# pcg_quad.net
KiCad netlist of a schematic drawn in EAGLE
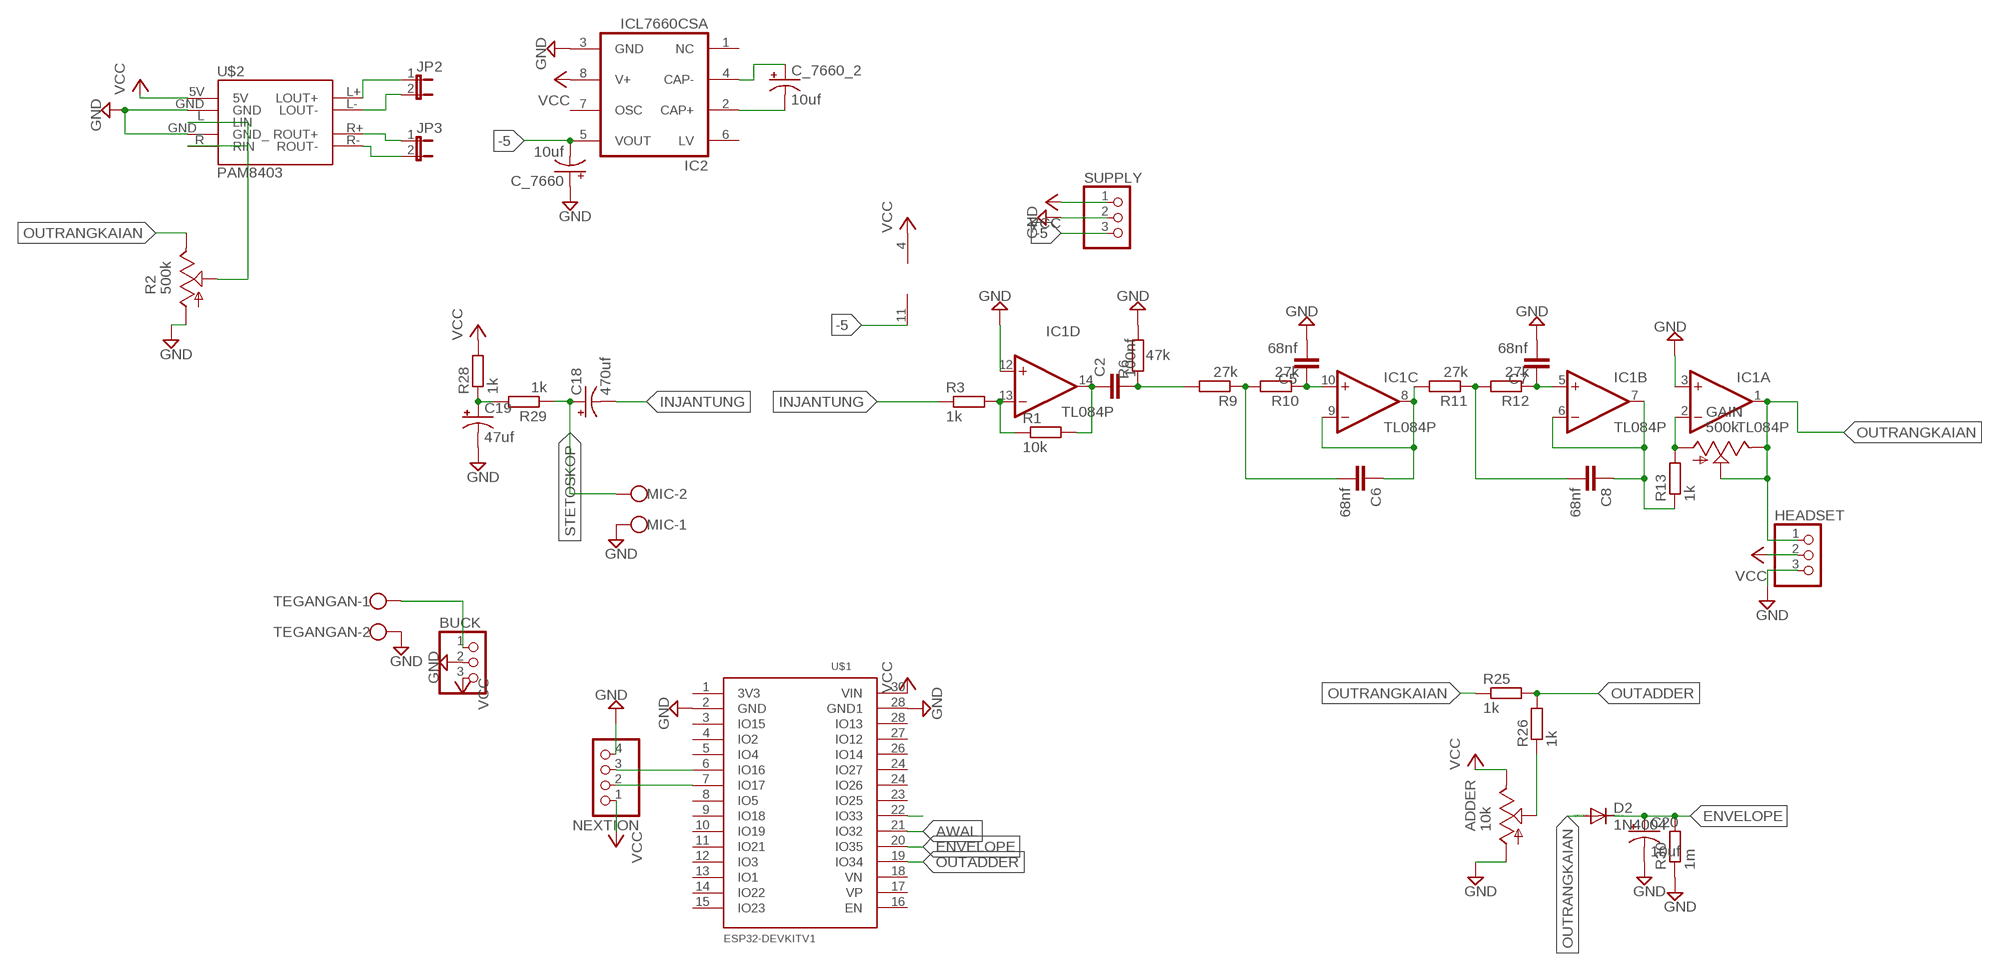
[diagram p0: schematic, sheet 1]

(export (version "E")
  (design (tool "Eeschema 10.0.6"))
  (components
    (comp (ref "ADDER")
      (value "10k")
      (footprint "eagle-import:B64Y")
      (libsource (lib "eagle-import") (part "TRIM_US-B64Y"))
    )
    (comp (ref "BUCK")
      (value "PINHD-1X3")
      (footprint "eagle-import:1X03")
      (libsource (lib "eagle-import") (part "PINHD-1X3"))
    )
    (comp (ref "C2")
      (value "100nf")
      (footprint "eagle-import:C050-025X075")
      (libsource (lib "eagle-import") (part "C-EU050-025X075"))
    )
    (comp (ref "C5")
      (value "68nf")
      (footprint "eagle-import:C050-025X075")
      (libsource (lib "eagle-import") (part "C-EU050-025X075"))
    )
    (comp (ref "C6")
      (value "68nf")
      (footprint "eagle-import:C050-025X075")
      (libsource (lib "eagle-import") (part "C-EU050-025X075"))
    )
    (comp (ref "C7")
      (value "68nf")
      (footprint "eagle-import:C050-025X075")
      (libsource (lib "eagle-import") (part "C-EU050-025X075"))
    )
    (comp (ref "C8")
      (value "68nf")
      (footprint "eagle-import:C050-025X075")
      (libsource (lib "eagle-import") (part "C-EU050-025X075"))
    )
    (comp (ref "C18")
      (value "470uf")
      (footprint "eagle-import:E2,5-7")
      (libsource (lib "eagle-import") (part "CPOL-USE2.5-7"))
    )
    (comp (ref "C19")
      (value "47uf")
      (footprint "eagle-import:E2-5")
      (libsource (lib "eagle-import") (part "CPOL-USE2-5"))
    )
    (comp (ref "C20")
      (value "10uf")
      (footprint "eagle-import:E2-5")
      (libsource (lib "eagle-import") (part "CPOL-USE2-5"))
    )
    (comp (ref "C_7660")
      (value "10uf")
      (footprint "eagle-import:E2-5")
      (libsource (lib "eagle-import") (part "CPOL-USE2-5"))
    )
    (comp (ref "C_7660_2")
      (value "10uf")
      (footprint "eagle-import:E2-5")
      (libsource (lib "eagle-import") (part "CPOL-USE2-5"))
    )
    (comp (ref "D2")
      (value "1N4004")
      (footprint "eagle-import:DO41-10")
      (libsource (lib "eagle-import") (part "1N4004"))
    )
    (comp (ref "GAIN")
      (value "500k")
      (footprint "eagle-import:B64Y")
      (libsource (lib "eagle-import") (part "TRIM_US-B64Y"))
    )
    (comp (ref "HEADSET")
      (value "PINHD-1X3")
      (footprint "eagle-import:1X03")
      (libsource (lib "eagle-import") (part "PINHD-1X3"))
    )
    (comp (ref "IC1")
      (value "TL084P")
      (footprint "eagle-import:DIL14")
      (libsource (lib "eagle-import") (part "TL084P"))
    )
    (comp (ref "IC2")
      (value "ICL7660CSA")
      (footprint "eagle-import:SO08")
      (fields (field (name "MF") "MAXIM"))
      (libsource (lib "eagle-import") (part "ICL7660CSA"))
    )
    (comp (ref "JP2")
      (value "JP1E")
      (footprint "eagle-import:JP1")
      (libsource (lib "eagle-import") (part "JP1E"))
    )
    (comp (ref "JP3")
      (value "JP1E")
      (footprint "eagle-import:JP1")
      (libsource (lib "eagle-import") (part "JP1E"))
    )
    (comp (ref "MIC")
      (value "W237-102")
      (footprint "eagle-import:W237-102")
      (fields (field (name "MPN") "237-102"))
      (libsource (lib "eagle-import") (part "W237-102"))
    )
    (comp (ref "NEXTION")
      (value "PINHD-1X4")
      (footprint "eagle-import:1X04")
      (libsource (lib "eagle-import") (part "PINHD-1X4"))
    )
    (comp (ref "R1")
      (value "10k")
      (footprint "eagle-import:0309_10")
      (libsource (lib "eagle-import") (part "R-EU_0309/10"))
    )
    (comp (ref "R2")
      (value "500k")
      (footprint "eagle-import:B64Y")
      (libsource (lib "eagle-import") (part "TRIM_US-B64Y"))
    )
    (comp (ref "R3")
      (value "1k")
      (footprint "eagle-import:0309_10")
      (libsource (lib "eagle-import") (part "R-EU_0309/10"))
    )
    (comp (ref "R6")
      (value "47k")
      (footprint "eagle-import:0309_10")
      (libsource (lib "eagle-import") (part "R-EU_0309/10"))
    )
    (comp (ref "R9")
      (value "27k")
      (footprint "eagle-import:0309_10")
      (libsource (lib "eagle-import") (part "R-EU_0309/10"))
    )
    (comp (ref "R10")
      (value "27k")
      (footprint "eagle-import:0309_10")
      (libsource (lib "eagle-import") (part "R-EU_0309/10"))
    )
    (comp (ref "R11")
      (value "27k")
      (footprint "eagle-import:0309_10")
      (libsource (lib "eagle-import") (part "R-EU_0309/10"))
    )
    (comp (ref "R12")
      (value "27k")
      (footprint "eagle-import:0309_10")
      (libsource (lib "eagle-import") (part "R-EU_0309/10"))
    )
    (comp (ref "R13")
      (value "1k")
      (footprint "eagle-import:0309_10")
      (libsource (lib "eagle-import") (part "R-EU_0309/10"))
    )
    (comp (ref "R25")
      (value "1k")
      (footprint "eagle-import:0309_10")
      (libsource (lib "eagle-import") (part "R-EU_0309/10"))
    )
    (comp (ref "R26")
      (value "1k")
      (footprint "eagle-import:0309_10")
      (libsource (lib "eagle-import") (part "R-EU_0309/10"))
    )
    (comp (ref "R28")
      (value "1k")
      (footprint "eagle-import:0309_10")
      (libsource (lib "eagle-import") (part "R-EU_0309/10"))
    )
    (comp (ref "R29")
      (value "1k")
      (footprint "eagle-import:0309_10")
      (libsource (lib "eagle-import") (part "R-EU_0309/10"))
    )
    (comp (ref "R30")
      (value "1m")
      (footprint "eagle-import:0309_10")
      (libsource (lib "eagle-import") (part "R-EU_0309/10"))
    )
    (comp (ref "SUPPLY")
      (value "PINHD-1X3")
      (footprint "eagle-import:1X03")
      (libsource (lib "eagle-import") (part "PINHD-1X3"))
    )
    (comp (ref "TEGANGAN")
      (value "W237-102")
      (footprint "eagle-import:W237-102")
      (fields (field (name "MPN") "237-102"))
      (libsource (lib "eagle-import") (part "W237-102"))
    )
    (comp (ref "U$1")
      (value "ESP32DEVKITV1")
      (footprint "eagle-import:ESP32-DEVKITV1")
      (libsource (lib "eagle-import") (part "ESP32DEVKITV1"))
    )
    (comp (ref "U$2")
      (value "PAM8403")
      (footprint "eagle-import:PAM8403")
      (libsource (lib "eagle-import") (part "PAM8403"))
    )
  )
  (nets
    (net (code "1") (name "-5") (class "Default")
      (node (ref "C_7660") (pin "-") (pinfunction "-_-") (pintype "passive"))
      (node (ref "IC1") (pin "11") (pinfunction "V-_11") (pintype "power_in"))
      (node (ref "IC2") (pin "5") (pinfunction "VOUT_5") (pintype "output"))
      (node (ref "SUPPLY") (pin "3") (pinfunction "3_3") (pintype "passive"))
    )
    (net (code "2") (name "AWAL") (class "Default")
      (node (ref "U$1") (pin "21") (pinfunction "IO32_21") (pintype "bidirectional"))
    )
    (net (code "3") (name "ENVELOPE") (class "Default")
      (node (ref "C20") (pin "+") (pinfunction "+_+") (pintype "passive"))
      (node (ref "D2") (pin "C") (pinfunction "C_C") (pintype "passive"))
      (node (ref "R30") (pin "2") (pinfunction "2_2") (pintype "passive"))
      (node (ref "U$1") (pin "20") (pinfunction "IO35_20") (pintype "bidirectional"))
    )
    (net (code "4") (name "GND") (class "Default")
      (node (ref "ADDER") (pin "A") (pinfunction "A_A") (pintype "passive"))
      (node (ref "BUCK") (pin "2") (pinfunction "2_2") (pintype "passive"))
      (node (ref "C19") (pin "-") (pinfunction "-_-") (pintype "passive"))
      (node (ref "C20") (pin "-") (pinfunction "-_-") (pintype "passive"))
      (node (ref "C5") (pin "2") (pinfunction "2_2") (pintype "passive"))
      (node (ref "C7") (pin "2") (pinfunction "2_2") (pintype "passive"))
      (node (ref "C_7660") (pin "+") (pinfunction "+_+") (pintype "passive"))
      (node (ref "HEADSET") (pin "3") (pinfunction "3_3") (pintype "passive"))
      (node (ref "IC1") (pin "12") (pinfunction "+IN_12") (pintype "input"))
      (node (ref "IC1") (pin "3") (pinfunction "+IN_3") (pintype "input"))
      (node (ref "IC2") (pin "3") (pinfunction "GND_3") (pintype "power_in"))
      (node (ref "MIC") (pin "1") (pinfunction "KL_1") (pintype "passive"))
      (node (ref "NEXTION") (pin "4") (pinfunction "4_4") (pintype "passive"))
      (node (ref "R2") (pin "A") (pinfunction "A_A") (pintype "passive"))
      (node (ref "R30") (pin "1") (pinfunction "1_1") (pintype "passive"))
      (node (ref "R6") (pin "2") (pinfunction "2_2") (pintype "passive"))
      (node (ref "SUPPLY") (pin "2") (pinfunction "2_2") (pintype "passive"))
      (node (ref "TEGANGAN") (pin "2") (pinfunction "KL_2") (pintype "passive"))
      (node (ref "U$1") (pin "2") (pinfunction "GND_2") (pintype "bidirectional"))
      (node (ref "U$1") (pin "28") (pinfunction "GND1_28") (pintype "bidirectional"))
      (node (ref "U$2") (pin "GND") (pinfunction "GND_GND") (pintype "bidirectional"))
      (node (ref "U$2") (pin "GND_") (pinfunction "GND__GND_") (pintype "bidirectional"))
    )
    (net (code "5") (name "INJANTUNG") (class "Default")
      (node (ref "C18") (pin "-") (pinfunction "-_-") (pintype "passive"))
      (node (ref "R3") (pin "1") (pinfunction "1_1") (pintype "passive"))
    )
    (net (code "6") (name "Net-(ADDER-PadS)") (class "Default")
      (node (ref "ADDER") (pin "S") (pinfunction "S_S") (pintype "passive"))
      (node (ref "R26") (pin "1") (pinfunction "1_1") (pintype "passive"))
    )
    (net (code "7") (name "Net-(C2-Pad2)") (class "Default")
      (node (ref "C2") (pin "2") (pinfunction "2_2") (pintype "passive"))
      (node (ref "R6") (pin "1") (pinfunction "1_1") (pintype "passive"))
      (node (ref "R9") (pin "2") (pinfunction "2_2") (pintype "passive"))
    )
    (net (code "8") (name "Net-(C6-Pad2)") (class "Default")
      (node (ref "C6") (pin "2") (pinfunction "2_2") (pintype "passive"))
      (node (ref "R10") (pin "2") (pinfunction "2_2") (pintype "passive"))
      (node (ref "R9") (pin "1") (pinfunction "1_1") (pintype "passive"))
    )
    (net (code "9") (name "Net-(C8-Pad2)") (class "Default")
      (node (ref "C8") (pin "2") (pinfunction "2_2") (pintype "passive"))
      (node (ref "R11") (pin "1") (pinfunction "1_1") (pintype "passive"))
      (node (ref "R12") (pin "2") (pinfunction "2_2") (pintype "passive"))
    )
    (net (code "10") (name "Net-(C19-Pad+)") (class "Default")
      (node (ref "C19") (pin "+") (pinfunction "+_+") (pintype "passive"))
      (node (ref "R28") (pin "1") (pinfunction "1_1") (pintype "passive"))
      (node (ref "R29") (pin "2") (pinfunction "2_2") (pintype "passive"))
    )
    (net (code "11") (name "Net-(IC1A--IN)") (class "Default")
      (node (ref "GAIN") (pin "A") (pinfunction "A_A") (pintype "passive"))
      (node (ref "IC1") (pin "2") (pinfunction "-IN_2") (pintype "input"))
      (node (ref "R13") (pin "2") (pinfunction "2_2") (pintype "passive"))
    )
    (net (code "12") (name "Net-(IC1B-+IN)") (class "Default")
      (node (ref "C7") (pin "1") (pinfunction "1_1") (pintype "passive"))
      (node (ref "IC1") (pin "5") (pinfunction "+IN_5") (pintype "input"))
      (node (ref "R12") (pin "1") (pinfunction "1_1") (pintype "passive"))
    )
    (net (code "13") (name "Net-(IC1B--IN)") (class "Default")
      (node (ref "C8") (pin "1") (pinfunction "1_1") (pintype "passive"))
      (node (ref "IC1") (pin "6") (pinfunction "-IN_6") (pintype "input"))
      (node (ref "IC1") (pin "7") (pinfunction "OUT_7") (pintype "output"))
      (node (ref "R13") (pin "1") (pinfunction "1_1") (pintype "passive"))
    )
    (net (code "14") (name "Net-(IC1C-+IN)") (class "Default")
      (node (ref "C5") (pin "1") (pinfunction "1_1") (pintype "passive"))
      (node (ref "IC1") (pin "10") (pinfunction "+IN_10") (pintype "input"))
      (node (ref "R10") (pin "1") (pinfunction "1_1") (pintype "passive"))
    )
    (net (code "15") (name "Net-(IC1C--IN)") (class "Default")
      (node (ref "C6") (pin "1") (pinfunction "1_1") (pintype "passive"))
      (node (ref "IC1") (pin "8") (pinfunction "OUT_8") (pintype "output"))
      (node (ref "IC1") (pin "9") (pinfunction "-IN_9") (pintype "input"))
      (node (ref "R11") (pin "2") (pinfunction "2_2") (pintype "passive"))
    )
    (net (code "16") (name "Net-(IC1D--IN)") (class "Default")
      (node (ref "IC1") (pin "13") (pinfunction "-IN_13") (pintype "input"))
      (node (ref "R1") (pin "1") (pinfunction "1_1") (pintype "passive"))
      (node (ref "R3") (pin "2") (pinfunction "2_2") (pintype "passive"))
    )
    (net (code "17") (name "Net-(IC1D-OUT)") (class "Default")
      (node (ref "C2") (pin "1") (pinfunction "1_1") (pintype "passive"))
      (node (ref "IC1") (pin "14") (pinfunction "OUT_14") (pintype "output"))
      (node (ref "R1") (pin "2") (pinfunction "2_2") (pintype "passive"))
    )
    (net (code "18") (name "Net-(IC2-CAP+)") (class "Default")
      (node (ref "C_7660_2") (pin "-") (pinfunction "-_-") (pintype "passive"))
      (node (ref "IC2") (pin "2") (pinfunction "CAP+_2") (pintype "passive"))
    )
    (net (code "19") (name "Net-(IC2-CAP-)") (class "Default")
      (node (ref "C_7660_2") (pin "+") (pinfunction "+_+") (pintype "passive"))
      (node (ref "IC2") (pin "4") (pinfunction "CAP-_4") (pintype "passive"))
    )
    (net (code "20") (name "Net-(TEGANGANA-KL)") (class "Default")
      (node (ref "BUCK") (pin "1") (pinfunction "1_1") (pintype "passive"))
      (node (ref "TEGANGAN") (pin "1") (pinfunction "KL_1") (pintype "passive"))
    )
    (net (code "21") (name "Net-(U$1-IO16)") (class "Default")
      (node (ref "NEXTION") (pin "3") (pinfunction "3_3") (pintype "passive"))
      (node (ref "U$1") (pin "6") (pinfunction "IO16_6") (pintype "bidirectional"))
    )
    (net (code "22") (name "Net-(U$1-IO17)") (class "Default")
      (node (ref "NEXTION") (pin "2") (pinfunction "2_2") (pintype "passive"))
      (node (ref "U$1") (pin "7") (pinfunction "IO17_7") (pintype "bidirectional"))
    )
    (net (code "23") (name "Net-(U$2-LIN)") (class "Default")
      (node (ref "R2") (pin "S") (pinfunction "S_S") (pintype "passive"))
      (node (ref "U$2") (pin "L") (pinfunction "LIN_L") (pintype "bidirectional"))
      (node (ref "U$2") (pin "R") (pinfunction "RIN_R") (pintype "bidirectional"))
    )
    (net (code "24") (name "Net-(U$2-LOUT+)") (class "Default")
      (node (ref "JP2") (pin "1") (pinfunction "1_1") (pintype "passive"))
      (node (ref "U$2") (pin "L+") (pinfunction "LOUT+_L+") (pintype "bidirectional"))
    )
    (net (code "25") (name "Net-(U$2-LOUT-)") (class "Default")
      (node (ref "JP2") (pin "2") (pinfunction "2_2") (pintype "passive"))
      (node (ref "U$2") (pin "L-") (pinfunction "LOUT-_L-") (pintype "bidirectional"))
    )
    (net (code "26") (name "Net-(U$2-ROUT+)") (class "Default")
      (node (ref "JP3") (pin "1") (pinfunction "1_1") (pintype "passive"))
      (node (ref "U$2") (pin "R+") (pinfunction "ROUT+_R+") (pintype "bidirectional"))
    )
    (net (code "27") (name "Net-(U$2-ROUT-)") (class "Default")
      (node (ref "JP3") (pin "2") (pinfunction "2_2") (pintype "passive"))
      (node (ref "U$2") (pin "R-") (pinfunction "ROUT-_R-") (pintype "bidirectional"))
    )
    (net (code "28") (name "OUTADDER") (class "Default")
      (node (ref "R25") (pin "2") (pinfunction "2_2") (pintype "passive"))
      (node (ref "R26") (pin "2") (pinfunction "2_2") (pintype "passive"))
      (node (ref "U$1") (pin "19") (pinfunction "IO34_19") (pintype "bidirectional"))
    )
    (net (code "29") (name "OUTRANGKAIAN") (class "Default")
      (node (ref "D2") (pin "A") (pinfunction "A_A") (pintype "passive"))
      (node (ref "GAIN") (pin "E") (pinfunction "E_E") (pintype "passive"))
      (node (ref "GAIN") (pin "S") (pinfunction "S_S") (pintype "passive"))
      (node (ref "HEADSET") (pin "1") (pinfunction "1_1") (pintype "passive"))
      (node (ref "IC1") (pin "1") (pinfunction "OUT_1") (pintype "output"))
      (node (ref "R2") (pin "E") (pinfunction "E_E") (pintype "passive"))
      (node (ref "R25") (pin "1") (pinfunction "1_1") (pintype "passive"))
    )
    (net (code "30") (name "STETOSKOP") (class "Default")
      (node (ref "C18") (pin "+") (pinfunction "+_+") (pintype "passive"))
      (node (ref "MIC") (pin "2") (pinfunction "KL_2") (pintype "passive"))
      (node (ref "R29") (pin "1") (pinfunction "1_1") (pintype "passive"))
    )
    (net (code "31") (name "VCC") (class "Default")
      (node (ref "ADDER") (pin "E") (pinfunction "E_E") (pintype "passive"))
      (node (ref "BUCK") (pin "3") (pinfunction "3_3") (pintype "passive"))
      (node (ref "HEADSET") (pin "2") (pinfunction "2_2") (pintype "passive"))
      (node (ref "IC1") (pin "4") (pinfunction "V+_4") (pintype "power_in"))
      (node (ref "IC2") (pin "8") (pinfunction "V+_8") (pintype "power_in"))
      (node (ref "NEXTION") (pin "1") (pinfunction "1_1") (pintype "passive"))
      (node (ref "R28") (pin "2") (pinfunction "2_2") (pintype "passive"))
      (node (ref "SUPPLY") (pin "1") (pinfunction "1_1") (pintype "passive"))
      (node (ref "U$1") (pin "30") (pinfunction "VIN_30") (pintype "bidirectional"))
      (node (ref "U$2") (pin "5V") (pinfunction "5V_5V") (pintype "bidirectional"))
    )
    (net (code "32") (name "unconnected-(IC2-LV-Pad6)") (class "Default")
      (node (ref "IC2") (pin "6") (pinfunction "LV_6") (pintype "passive"))
    )
    (net (code "33") (name "unconnected-(IC2-NC-Pad1)") (class "Default")
      (node (ref "IC2") (pin "1") (pinfunction "NC_1") (pintype "no_connect"))
    )
    (net (code "34") (name "unconnected-(IC2-OSC-Pad7)") (class "Default")
      (node (ref "IC2") (pin "7") (pinfunction "OSC_7") (pintype "output"))
    )
    (net (code "35") (name "unconnected-(U$1-3V3-Pad1)") (class "Default")
      (node (ref "U$1") (pin "1") (pinfunction "3V3_1") (pintype "bidirectional"))
    )
    (net (code "36") (name "unconnected-(U$1-EN-Pad16)") (class "Default")
      (node (ref "U$1") (pin "16") (pinfunction "EN_16") (pintype "bidirectional"))
    )
    (net (code "37") (name "unconnected-(U$1-IO1-Pad13)") (class "Default")
      (node (ref "U$1") (pin "13") (pinfunction "IO1_13") (pintype "bidirectional"))
    )
    (net (code "38") (name "unconnected-(U$1-IO2-Pad4)") (class "Default")
      (node (ref "U$1") (pin "4") (pinfunction "IO2_4") (pintype "bidirectional"))
    )
    (net (code "39") (name "unconnected-(U$1-IO3-Pad12)") (class "Default")
      (node (ref "U$1") (pin "12") (pinfunction "IO3_12") (pintype "bidirectional"))
    )
    (net (code "40") (name "unconnected-(U$1-IO4-Pad5)") (class "Default")
      (node (ref "U$1") (pin "5") (pinfunction "IO4_5") (pintype "bidirectional"))
    )
    (net (code "41") (name "unconnected-(U$1-IO5-Pad8)") (class "Default")
      (node (ref "U$1") (pin "8") (pinfunction "IO5_8") (pintype "bidirectional"))
    )
    (net (code "42") (name "unconnected-(U$1-IO12-Pad27)") (class "Default")
      (node (ref "U$1") (pin "27") (pinfunction "IO12_27") (pintype "bidirectional"))
    )
    (net (code "43") (name "unconnected-(U$1-IO13-Pad28)") (class "Default")
      (node (ref "U$1") (pin "28") (pinfunction "IO13_28") (pintype "bidirectional"))
    )
    (net (code "44") (name "unconnected-(U$1-IO14-Pad26)") (class "Default")
      (node (ref "U$1") (pin "26") (pinfunction "IO14_26") (pintype "bidirectional"))
    )
    (net (code "45") (name "unconnected-(U$1-IO15-Pad3)") (class "Default")
      (node (ref "U$1") (pin "3") (pinfunction "IO15_3") (pintype "bidirectional"))
    )
    (net (code "46") (name "unconnected-(U$1-IO18-Pad9)") (class "Default")
      (node (ref "U$1") (pin "9") (pinfunction "IO18_9") (pintype "bidirectional"))
    )
    (net (code "47") (name "unconnected-(U$1-IO19-Pad10)") (class "Default")
      (node (ref "U$1") (pin "10") (pinfunction "IO19_10") (pintype "bidirectional"))
    )
    (net (code "48") (name "unconnected-(U$1-IO21-Pad11)") (class "Default")
      (node (ref "U$1") (pin "11") (pinfunction "IO21_11") (pintype "bidirectional"))
    )
    (net (code "49") (name "unconnected-(U$1-IO22-Pad14)") (class "Default")
      (node (ref "U$1") (pin "14") (pinfunction "IO22_14") (pintype "bidirectional"))
    )
    (net (code "50") (name "unconnected-(U$1-IO23-Pad15)") (class "Default")
      (node (ref "U$1") (pin "15") (pinfunction "IO23_15") (pintype "bidirectional"))
    )
    (net (code "51") (name "unconnected-(U$1-IO25-Pad23)") (class "Default")
      (node (ref "U$1") (pin "23") (pinfunction "IO25_23") (pintype "bidirectional"))
    )
    (net (code "52") (name "unconnected-(U$1-IO26-Pad24)") (class "Default")
      (node (ref "U$1") (pin "24") (pinfunction "IO26_24") (pintype "bidirectional"))
    )
    (net (code "53") (name "unconnected-(U$1-IO27-Pad24)") (class "Default")
      (node (ref "U$1") (pin "24") (pinfunction "IO27_24") (pintype "bidirectional"))
    )
    (net (code "54") (name "unconnected-(U$1-IO33-Pad22)") (class "Default")
      (node (ref "U$1") (pin "22") (pinfunction "IO33_22") (pintype "bidirectional"))
    )
    (net (code "55") (name "unconnected-(U$1-VN-Pad18)") (class "Default")
      (node (ref "U$1") (pin "18") (pinfunction "VN_18") (pintype "bidirectional"))
    )
    (net (code "56") (name "unconnected-(U$1-VP-Pad17)") (class "Default")
      (node (ref "U$1") (pin "17") (pinfunction "VP_17") (pintype "bidirectional"))
    )
  )
)
